# SLO.net
KiCad netlist of a schematic drawn in Altium Designer
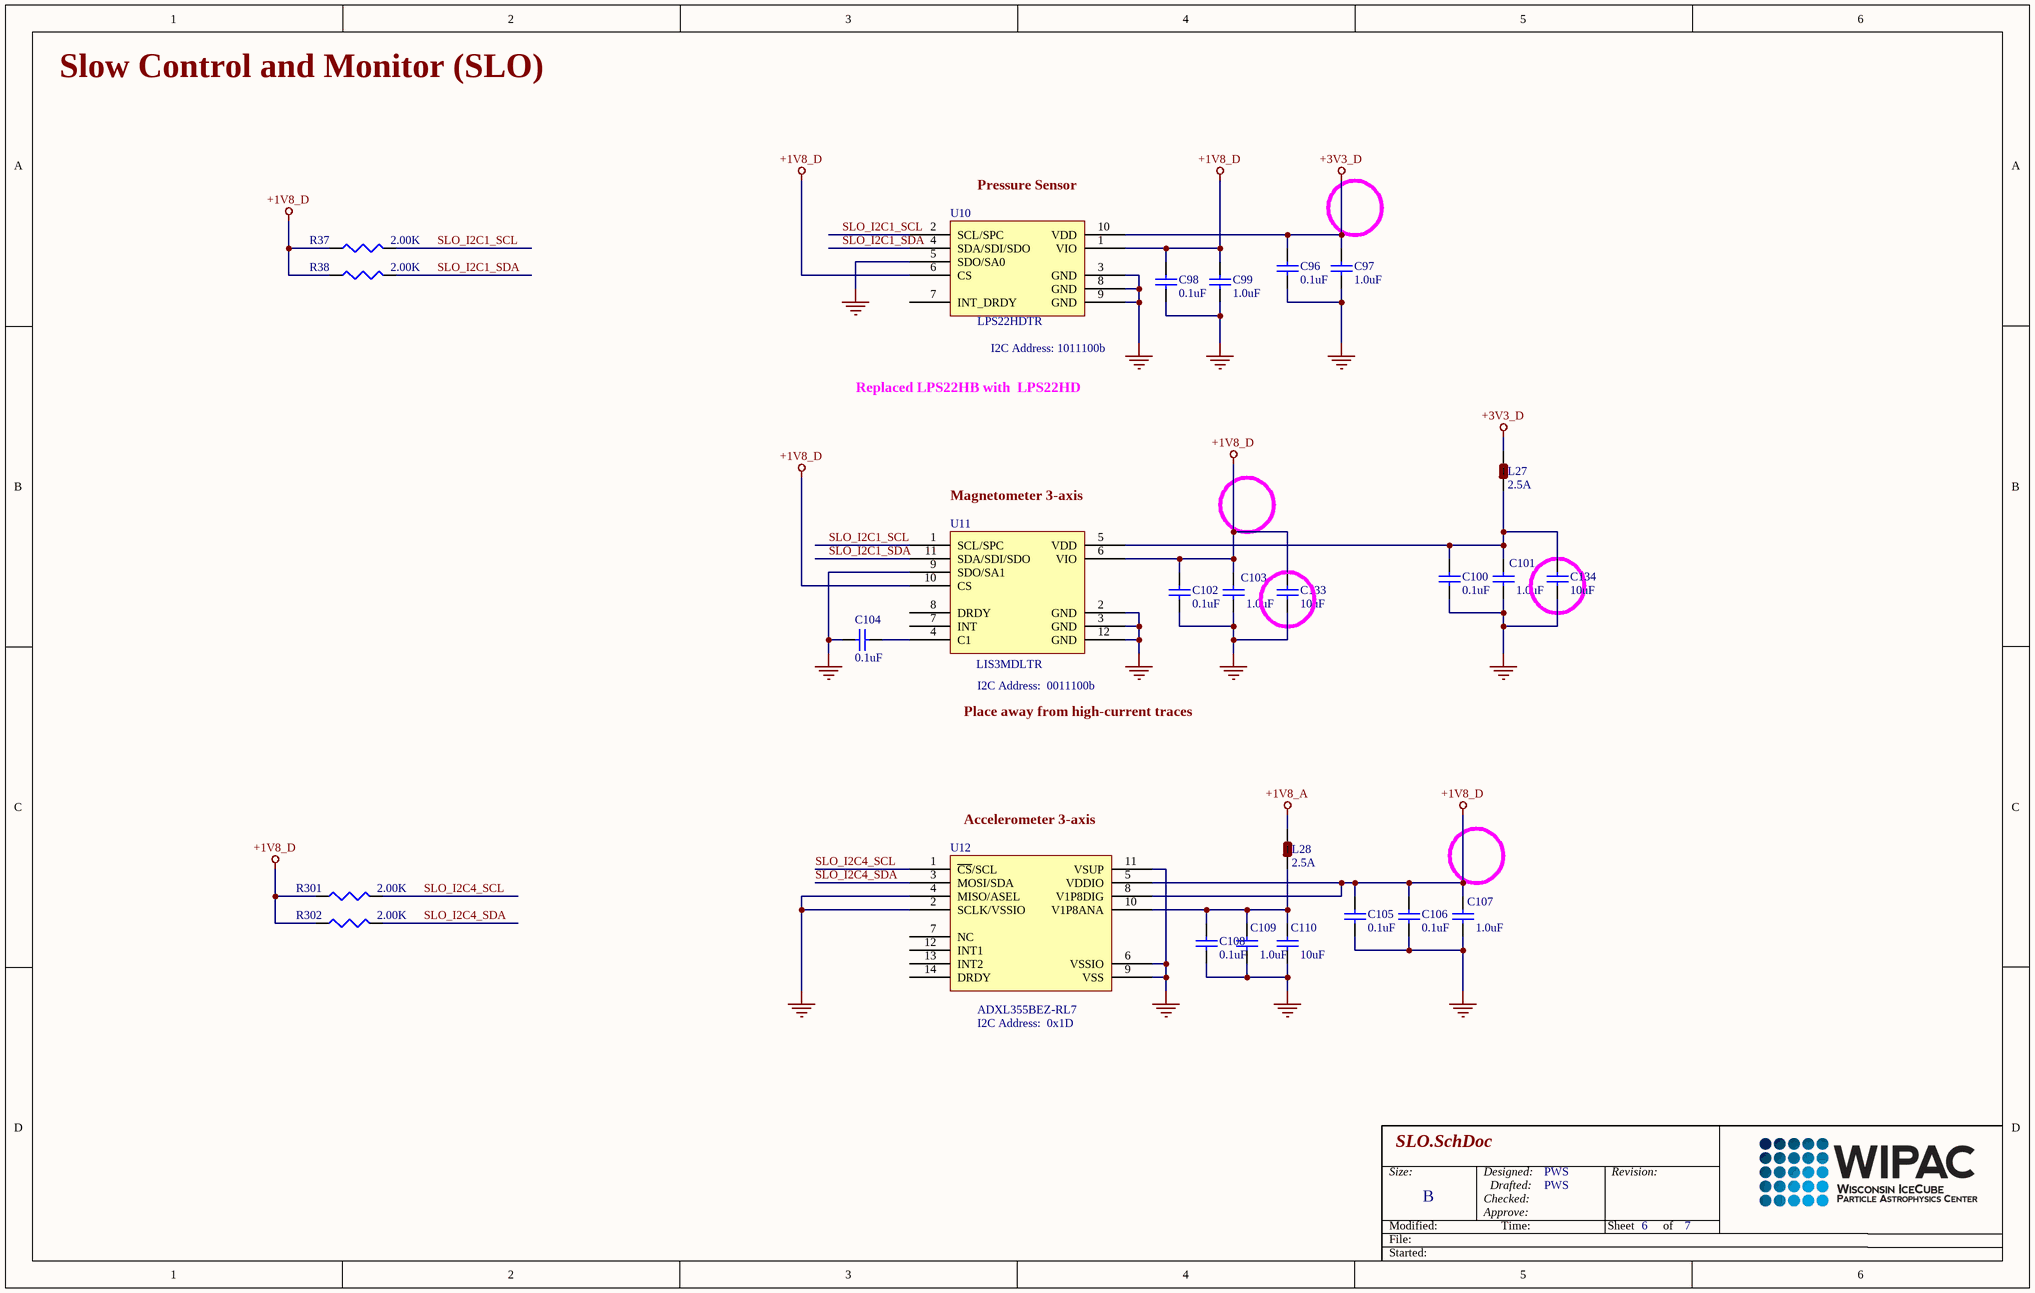
[diagram p0: SLO.SchDoc]

(export (version "E")
  (design (tool "Eeschema 10.0.6"))
  (components
    (comp (ref "C96")
      (value "0.1uF_603_50V")
      (footprint "CAPC_0603")
      (description "0.1µF ±10% 50V Ceramic Capacitor X7R 0603 (1608 Metric)")
      (fields
        (field (name "MANUFACTURER") "TDK")
        (field (name "MANUFACTURER PART NUMBER") "CGJ3E2X7R1H104K080AA")
        (field (name "CAPACITANCE") "0.1uF")
      )
      (libsource (lib "Custom1") (part "CapC_0.1uF_603_50V"))
    )
    (comp (ref "C97")
      (value "1.0uF_603_25V")
      (footprint "CAPC_0603")
      (description "1µF ±10% 25V Ceramic Capacitor X7R 0603 (1608 Metric)")
      (fields
        (field (name "MANUFACTURER") "Murata")
        (field (name "MANUFACTURER PART NUMBER") "GCJ188R71E105KA01D")
        (field (name "CAPACITANCE") "1.0uF")
      )
      (libsource (lib "Custom1") (part "CapC_1.0uF_603_25V"))
    )
    (comp (ref "C98")
      (value "0.1uF_603_50V")
      (footprint "CAPC_0603")
      (description "0.1µF ±10% 50V Ceramic Capacitor X7R 0603 (1608 Metric)")
      (fields
        (field (name "MANUFACTURER") "TDK")
        (field (name "MANUFACTURER PART NUMBER") "CGJ3E2X7R1H104K080AA")
        (field (name "CAPACITANCE") "0.1uF")
      )
      (libsource (lib "Custom1") (part "CapC_0.1uF_603_50V"))
    )
    (comp (ref "C99")
      (value "1.0uF_603_25V")
      (footprint "CAPC_0603")
      (description "1µF ±10% 25V Ceramic Capacitor X7R 0603 (1608 Metric)")
      (fields
        (field (name "MANUFACTURER") "Murata")
        (field (name "MANUFACTURER PART NUMBER") "GCJ188R71E105KA01D")
        (field (name "CAPACITANCE") "1.0uF")
      )
      (libsource (lib "Custom1") (part "CapC_1.0uF_603_25V"))
    )
    (comp (ref "C100")
      (value "0.1uF_603_50V")
      (footprint "CAPC_0603")
      (description "0.1µF ±10% 50V Ceramic Capacitor X7R 0603 (1608 Metric)")
      (fields
        (field (name "MANUFACTURER") "TDK")
        (field (name "MANUFACTURER PART NUMBER") "CGJ3E2X7R1H104K080AA")
        (field (name "CAPACITANCE") "0.1uF")
      )
      (libsource (lib "Custom1") (part "CapC_0.1uF_603_50V"))
    )
    (comp (ref "C101")
      (value "1.0uF_603_25V")
      (footprint "CAPC_0603")
      (description "1µF ±10% 25V Ceramic Capacitor X7R 0603 (1608 Metric)")
      (fields
        (field (name "MANUFACTURER") "Murata")
        (field (name "MANUFACTURER PART NUMBER") "GCJ188R71E105KA01D")
        (field (name "CAPACITANCE") "1.0uF")
      )
      (libsource (lib "Custom1") (part "CapC_1.0uF_603_25V"))
    )
    (comp (ref "C102")
      (value "0.1uF_603_50V")
      (footprint "CAPC_0603")
      (description "0.1µF ±10% 50V Ceramic Capacitor X7R 0603 (1608 Metric)")
      (fields
        (field (name "MANUFACTURER") "TDK")
        (field (name "MANUFACTURER PART NUMBER") "CGJ3E2X7R1H104K080AA")
        (field (name "CAPACITANCE") "0.1uF")
      )
      (libsource (lib "Custom1") (part "CapC_0.1uF_603_50V"))
    )
    (comp (ref "C103")
      (value "1.0uF_603_25V")
      (footprint "CAPC_0603")
      (description "1µF ±10% 25V Ceramic Capacitor X7R 0603 (1608 Metric)")
      (fields
        (field (name "MANUFACTURER") "Murata")
        (field (name "MANUFACTURER PART NUMBER") "GCJ188R71E105KA01D")
        (field (name "CAPACITANCE") "1.0uF")
      )
      (libsource (lib "Custom1") (part "CapC_1.0uF_603_25V"))
    )
    (comp (ref "C104")
      (value "0.1uF_603_50V")
      (footprint "CAPC_0603")
      (description "0.1µF ±10% 50V Ceramic Capacitor X7R 0603 (1608 Metric)")
      (fields
        (field (name "MANUFACTURER") "TDK")
        (field (name "MANUFACTURER PART NUMBER") "CGJ3E2X7R1H104K080AA")
        (field (name "CAPACITANCE") "0.1uF")
      )
      (libsource (lib "Custom1") (part "CapC_0.1uF_603_50V"))
    )
    (comp (ref "C105")
      (value "0.1uF_603_50V")
      (footprint "CAPC_0603")
      (description "0.1µF ±10% 50V Ceramic Capacitor X7R 0603 (1608 Metric)")
      (fields
        (field (name "MANUFACTURER") "TDK")
        (field (name "MANUFACTURER PART NUMBER") "CGJ3E2X7R1H104K080AA")
        (field (name "CAPACITANCE") "0.1uF")
      )
      (libsource (lib "Custom1") (part "CapC_0.1uF_603_50V"))
    )
    (comp (ref "C106")
      (value "0.1uF_603_50V")
      (footprint "CAPC_0603")
      (description "0.1µF ±10% 50V Ceramic Capacitor X7R 0603 (1608 Metric)")
      (fields
        (field (name "MANUFACTURER") "TDK")
        (field (name "MANUFACTURER PART NUMBER") "CGJ3E2X7R1H104K080AA")
        (field (name "CAPACITANCE") "0.1uF")
      )
      (libsource (lib "Custom1") (part "CapC_0.1uF_603_50V"))
    )
    (comp (ref "C107")
      (value "1.0uF_603_25V")
      (footprint "CAPC_0603")
      (description "1µF ±10% 25V Ceramic Capacitor X7R 0603 (1608 Metric)")
      (fields
        (field (name "MANUFACTURER") "Murata")
        (field (name "MANUFACTURER PART NUMBER") "GCJ188R71E105KA01D")
        (field (name "CAPACITANCE") "1.0uF")
      )
      (libsource (lib "Custom1") (part "CapC_1.0uF_603_25V"))
    )
    (comp (ref "C108")
      (value "0.1uF_603_50V")
      (footprint "CAPC_0603")
      (description "0.1µF ±10% 50V Ceramic Capacitor X7R 0603 (1608 Metric)")
      (fields
        (field (name "MANUFACTURER") "TDK")
        (field (name "MANUFACTURER PART NUMBER") "CGJ3E2X7R1H104K080AA")
        (field (name "CAPACITANCE") "0.1uF")
      )
      (libsource (lib "Custom1") (part "CapC_0.1uF_603_50V"))
    )
    (comp (ref "C109")
      (value "1.0uF_603_25V")
      (footprint "CAPC_0603")
      (description "1µF ±10% 25V Ceramic Capacitor X7R 0603 (1608 Metric)")
      (fields
        (field (name "MANUFACTURER") "Murata")
        (field (name "MANUFACTURER PART NUMBER") "GCJ188R71E105KA01D")
        (field (name "CAPACITANCE") "1.0uF")
      )
      (libsource (lib "Custom1") (part "CapC_1.0uF_603_25V"))
    )
    (comp (ref "C110")
      (value "10uF_805_10V")
      (footprint "CAPC_0805")
      (description "Capacitor")
      (fields
        (field (name "MANUFACTURER") "Murata")
        (field (name "MANUFACTURER PART NUMBER") "GCJ21BR71A106KE01L")
        (field (name "CAPACITANCE") "10uF")
      )
      (libsource (lib "Custom1") (part "CapC_10uF_805_10V"))
    )
    (comp (ref "C133")
      (value "10uF_805_10V")
      (footprint "CAPC_0805")
      (description "Capacitor")
      (fields
        (field (name "MANUFACTURER") "Murata")
        (field (name "MANUFACTURER PART NUMBER") "GCJ21BR71A106KE01L")
        (field (name "CAPACITANCE") "10uF")
      )
      (libsource (lib "Custom1") (part "CapC_10uF_805_10V"))
    )
    (comp (ref "C134")
      (value "10uF_805_10V")
      (footprint "CAPC_0805")
      (description "Capacitor")
      (fields
        (field (name "MANUFACTURER") "Murata")
        (field (name "MANUFACTURER PART NUMBER") "GCJ21BR71A106KE01L")
        (field (name "CAPACITANCE") "10uF")
      )
      (libsource (lib "Custom1") (part "CapC_10uF_805_10V"))
    )
    (comp (ref "L27")
      (value "2.5A_Bead_0805")
      (footprint "SMD-0805")
      (description "MPZ2012S331ATD25")
      (fields
        (field (name "MANUFACTURER") "TDK")
        (field (name "TOLERANCE") "25%")
        (field (name "MAX CURRENT RATING") "2.5A")
      )
      (libsource (lib "Custom1") (part "Bead SM_805_2.5A_TDK"))
    )
    (comp (ref "L28")
      (value "2.5A_Bead_0805")
      (footprint "SMD-0805")
      (description "MPZ2012S331ATD25")
      (fields
        (field (name "MANUFACTURER") "TDK")
        (field (name "TOLERANCE") "25%")
        (field (name "MAX CURRENT RATING") "2.5A")
      )
      (libsource (lib "Custom1") (part "Bead SM_805_2.5A_TDK"))
    )
    (comp (ref "R37")
      (value "R_2.00K_603_1%")
      (footprint "RES_0603")
      (description "RES 2.00K OHM 1/10W 1% 0603 SMD")
      (fields
        (field (name "MANUFACTURER") "Panasonic")
        (field (name "MANUFACTURER PART NUMBER") "ERJ3EKF2001V")
        (field (name "RESISTANCE") "2.00K")
      )
      (libsource (lib "Custom1") (part "R_2.00K_603_1%"))
    )
    (comp (ref "R38")
      (value "R_2.00K_603_1%")
      (footprint "RES_0603")
      (description "RES 2.00K OHM 1/10W 1% 0603 SMD")
      (fields
        (field (name "MANUFACTURER") "Panasonic")
        (field (name "MANUFACTURER PART NUMBER") "ERJ3EKF2001V")
        (field (name "RESISTANCE") "2.00K")
      )
      (libsource (lib "Custom1") (part "R_2.00K_603_1%"))
    )
    (comp (ref "R301")
      (value "R_2.00K_603_1%")
      (footprint "RES_0603")
      (description "RES 2.00K OHM 1/10W 1% 0603 SMD")
      (fields
        (field (name "MANUFACTURER") "Panasonic")
        (field (name "MANUFACTURER PART NUMBER") "ERJ3EKF2001V")
        (field (name "RESISTANCE") "2.00K")
      )
      (libsource (lib "Custom1") (part "R_2.00K_603_1%"))
    )
    (comp (ref "R302")
      (value "R_2.00K_603_1%")
      (footprint "RES_0603")
      (description "RES 2.00K OHM 1/10W 1% 0603 SMD")
      (fields
        (field (name "MANUFACTURER") "Panasonic")
        (field (name "MANUFACTURER PART NUMBER") "ERJ3EKF2001V")
        (field (name "RESISTANCE") "2.00K")
      )
      (libsource (lib "Custom1") (part "R_2.00K_603_1%"))
    )
    (comp (ref "U10")
      (value "LPS22HDTR")
      (footprint "HLGA-10L")
      (description "Pressure Sensor  Absolute   10-VFLGA")
      (fields (field (name "MANUFACTURER") "STMicroelectronics"))
      (libsource (lib "Custom1") (part "LPS22HDTR"))
    )
    (comp (ref "U11")
      (value "LIS3MDLTR")
      (footprint "VFLGA-12")
      (description "Magnetoresistive Sensor X, Y, Z Axis 12-LGA (2x2)")
      (fields (field (name "MANUFACTURER") "STMicroelectronics"))
      (libsource (lib "Custom1") (part "LIS3MDLTR"))
    )
    (comp (ref "U12")
      (value "ADXL355BEZ-RL7")
      (footprint "E-14-1")
      (description "Accelerometer X, Y, Z Axis ±2g, 4g, 8g 1.5kHz 14-CLCC (6x6)")
      (fields (field (name "MANUFACTURER") "Analog Devices"))
      (libsource (lib "Custom1") (part "ADXL355BEZ-RL7"))
    )
  )
  (nets
    (net (code "1") (name "+1V8_A") (class "Default")
      (node (ref "L28") (pin "2") (pinfunction "2_2") (pintype "passive"))
    )
    (net (code "2") (name "+1V8_D") (class "Default")
      (node (ref "C102") (pin "2") (pinfunction "2_2") (pintype "passive"))
      (node (ref "C103") (pin "2") (pinfunction "2_2") (pintype "passive"))
      (node (ref "C105") (pin "2") (pinfunction "2_2") (pintype "passive"))
      (node (ref "C106") (pin "2") (pinfunction "2_2") (pintype "passive"))
      (node (ref "C107") (pin "2") (pinfunction "2_2") (pintype "passive"))
      (node (ref "C133") (pin "2") (pinfunction "2_2") (pintype "passive"))
      (node (ref "C98") (pin "2") (pinfunction "2_2") (pintype "passive"))
      (node (ref "C99") (pin "2") (pinfunction "2_2") (pintype "passive"))
      (node (ref "R301") (pin "1") (pinfunction "1_1") (pintype "passive"))
      (node (ref "R302") (pin "1") (pinfunction "1_1") (pintype "passive"))
      (node (ref "R37") (pin "1") (pinfunction "1_1") (pintype "passive"))
      (node (ref "R38") (pin "1") (pinfunction "1_1") (pintype "passive"))
      (node (ref "U10") (pin "1") (pinfunction "VIO_1") (pintype "passive"))
      (node (ref "U10") (pin "6") (pinfunction "CS_6") (pintype "passive"))
      (node (ref "U11") (pin "10") (pinfunction "CS_10") (pintype "passive"))
      (node (ref "U11") (pin "6") (pinfunction "VIO_6") (pintype "passive"))
      (node (ref "U12") (pin "5") (pinfunction "VDDIO_5") (pintype "passive"))
      (node (ref "U12") (pin "8") (pinfunction "V1P8DIG_8") (pintype "passive"))
    )
    (net (code "3") (name "+3V3_D") (class "Default")
      (node (ref "C96") (pin "2") (pinfunction "2_2") (pintype "passive"))
      (node (ref "C97") (pin "2") (pinfunction "2_2") (pintype "passive"))
      (node (ref "L27") (pin "2") (pinfunction "2_2") (pintype "passive"))
      (node (ref "U10") (pin "10") (pinfunction "VDD_10") (pintype "passive"))
    )
    (net (code "4") (name "/SLO_I2C1_SCL") (class "Default")
      (node (ref "R37") (pin "2") (pinfunction "2_2") (pintype "passive"))
      (node (ref "U10") (pin "2") (pinfunction "SCL/SPC_2") (pintype "passive"))
      (node (ref "U11") (pin "1") (pinfunction "SCL/SPC_1") (pintype "passive"))
    )
    (net (code "5") (name "/SLO_I2C1_SDA") (class "Default")
      (node (ref "R38") (pin "2") (pinfunction "2_2") (pintype "passive"))
      (node (ref "U10") (pin "4") (pinfunction "SDA/SDI/SDO_4") (pintype "passive"))
      (node (ref "U11") (pin "11") (pinfunction "SDA/SDI/SDO_11") (pintype "passive"))
    )
    (net (code "6") (name "/SLO_I2C4_SCL") (class "Default")
      (node (ref "R301") (pin "2") (pinfunction "2_2") (pintype "passive"))
      (node (ref "U12") (pin "1") (pinfunction "~{CS}/SCL_1") (pintype "passive"))
    )
    (net (code "7") (name "/SLO_I2C4_SDA") (class "Default")
      (node (ref "R302") (pin "2") (pinfunction "2_2") (pintype "passive"))
      (node (ref "U12") (pin "3") (pinfunction "MOSI/SDA_3") (pintype "passive"))
    )
    (net (code "8") (name "GND") (class "Default")
      (node (ref "C100") (pin "1") (pinfunction "1_1") (pintype "passive"))
      (node (ref "C101") (pin "1") (pinfunction "1_1") (pintype "passive"))
      (node (ref "C102") (pin "1") (pinfunction "1_1") (pintype "passive"))
      (node (ref "C103") (pin "1") (pinfunction "1_1") (pintype "passive"))
      (node (ref "C104") (pin "2") (pinfunction "2_2") (pintype "passive"))
      (node (ref "C105") (pin "1") (pinfunction "1_1") (pintype "passive"))
      (node (ref "C106") (pin "1") (pinfunction "1_1") (pintype "passive"))
      (node (ref "C107") (pin "1") (pinfunction "1_1") (pintype "passive"))
      (node (ref "C108") (pin "1") (pinfunction "1_1") (pintype "passive"))
      (node (ref "C109") (pin "1") (pinfunction "1_1") (pintype "passive"))
      (node (ref "C110") (pin "1") (pinfunction "1_1") (pintype "passive"))
      (node (ref "C133") (pin "1") (pinfunction "1_1") (pintype "passive"))
      (node (ref "C134") (pin "1") (pinfunction "1_1") (pintype "passive"))
      (node (ref "C96") (pin "1") (pinfunction "1_1") (pintype "passive"))
      (node (ref "C97") (pin "1") (pinfunction "1_1") (pintype "passive"))
      (node (ref "C98") (pin "1") (pinfunction "1_1") (pintype "passive"))
      (node (ref "C99") (pin "1") (pinfunction "1_1") (pintype "passive"))
      (node (ref "U10") (pin "3") (pinfunction "GND_3") (pintype "passive"))
      (node (ref "U10") (pin "5") (pinfunction "SDO/SA0_5") (pintype "passive"))
      (node (ref "U10") (pin "8") (pinfunction "GND_8") (pintype "passive"))
      (node (ref "U10") (pin "9") (pinfunction "GND_9") (pintype "passive"))
      (node (ref "U11") (pin "12") (pinfunction "GND_12") (pintype "passive"))
      (node (ref "U11") (pin "2") (pinfunction "GND_2") (pintype "passive"))
      (node (ref "U11") (pin "3") (pinfunction "GND_3") (pintype "passive"))
      (node (ref "U11") (pin "9") (pinfunction "SDO/SA1_9") (pintype "passive"))
      (node (ref "U12") (pin "11") (pinfunction "VSUP_11") (pintype "passive"))
      (node (ref "U12") (pin "2") (pinfunction "SCLK/VSSIO_2") (pintype "passive"))
      (node (ref "U12") (pin "4") (pinfunction "MISO/ASEL_4") (pintype "passive"))
      (node (ref "U12") (pin "6") (pinfunction "VSSIO_6") (pintype "passive"))
      (node (ref "U12") (pin "9") (pinfunction "VSS_9") (pintype "passive"))
    )
    (net (code "9") (name "Net-(U11-C1)") (class "Default")
      (node (ref "C104") (pin "1") (pinfunction "1_1") (pintype "passive"))
      (node (ref "U11") (pin "4") (pinfunction "C1_4") (pintype "passive"))
    )
    (net (code "10") (name "Net-(U11-VDD)") (class "Default")
      (node (ref "C100") (pin "2") (pinfunction "2_2") (pintype "passive"))
      (node (ref "C101") (pin "2") (pinfunction "2_2") (pintype "passive"))
      (node (ref "C134") (pin "2") (pinfunction "2_2") (pintype "passive"))
      (node (ref "L27") (pin "1") (pinfunction "1_1") (pintype "passive"))
      (node (ref "U11") (pin "5") (pinfunction "VDD_5") (pintype "passive"))
    )
    (net (code "11") (name "Net-(U12-V1P8ANA)") (class "Default")
      (node (ref "C108") (pin "2") (pinfunction "2_2") (pintype "passive"))
      (node (ref "C109") (pin "2") (pinfunction "2_2") (pintype "passive"))
      (node (ref "C110") (pin "2") (pinfunction "2_2") (pintype "passive"))
      (node (ref "L28") (pin "1") (pinfunction "1_1") (pintype "passive"))
      (node (ref "U12") (pin "10") (pinfunction "V1P8ANA_10") (pintype "passive"))
    )
    (net (code "12") (name "unconnected-(U10-INT_DRDY-Pad7)") (class "Default")
      (node (ref "U10") (pin "7") (pinfunction "INT_DRDY_7") (pintype "passive"))
    )
    (net (code "13") (name "unconnected-(U11-DRDY-Pad8)") (class "Default")
      (node (ref "U11") (pin "8") (pinfunction "DRDY_8") (pintype "passive"))
    )
    (net (code "14") (name "unconnected-(U11-INT-Pad7)") (class "Default")
      (node (ref "U11") (pin "7") (pinfunction "INT_7") (pintype "passive"))
    )
    (net (code "15") (name "unconnected-(U12-DRDY-Pad14)") (class "Default")
      (node (ref "U12") (pin "14") (pinfunction "DRDY_14") (pintype "passive"))
    )
    (net (code "16") (name "unconnected-(U12-INT1-Pad12)") (class "Default")
      (node (ref "U12") (pin "12") (pinfunction "INT1_12") (pintype "passive"))
    )
    (net (code "17") (name "unconnected-(U12-INT2-Pad13)") (class "Default")
      (node (ref "U12") (pin "13") (pinfunction "INT2_13") (pintype "passive"))
    )
    (net (code "18") (name "unconnected-(U12-NC-Pad7)") (class "Default")
      (node (ref "U12") (pin "7") (pinfunction "NC_7") (pintype "passive"))
    )
  )
)
